# ZED_BREAKOUT_v22.net
KiCad netlist of a schematic drawn in EAGLE
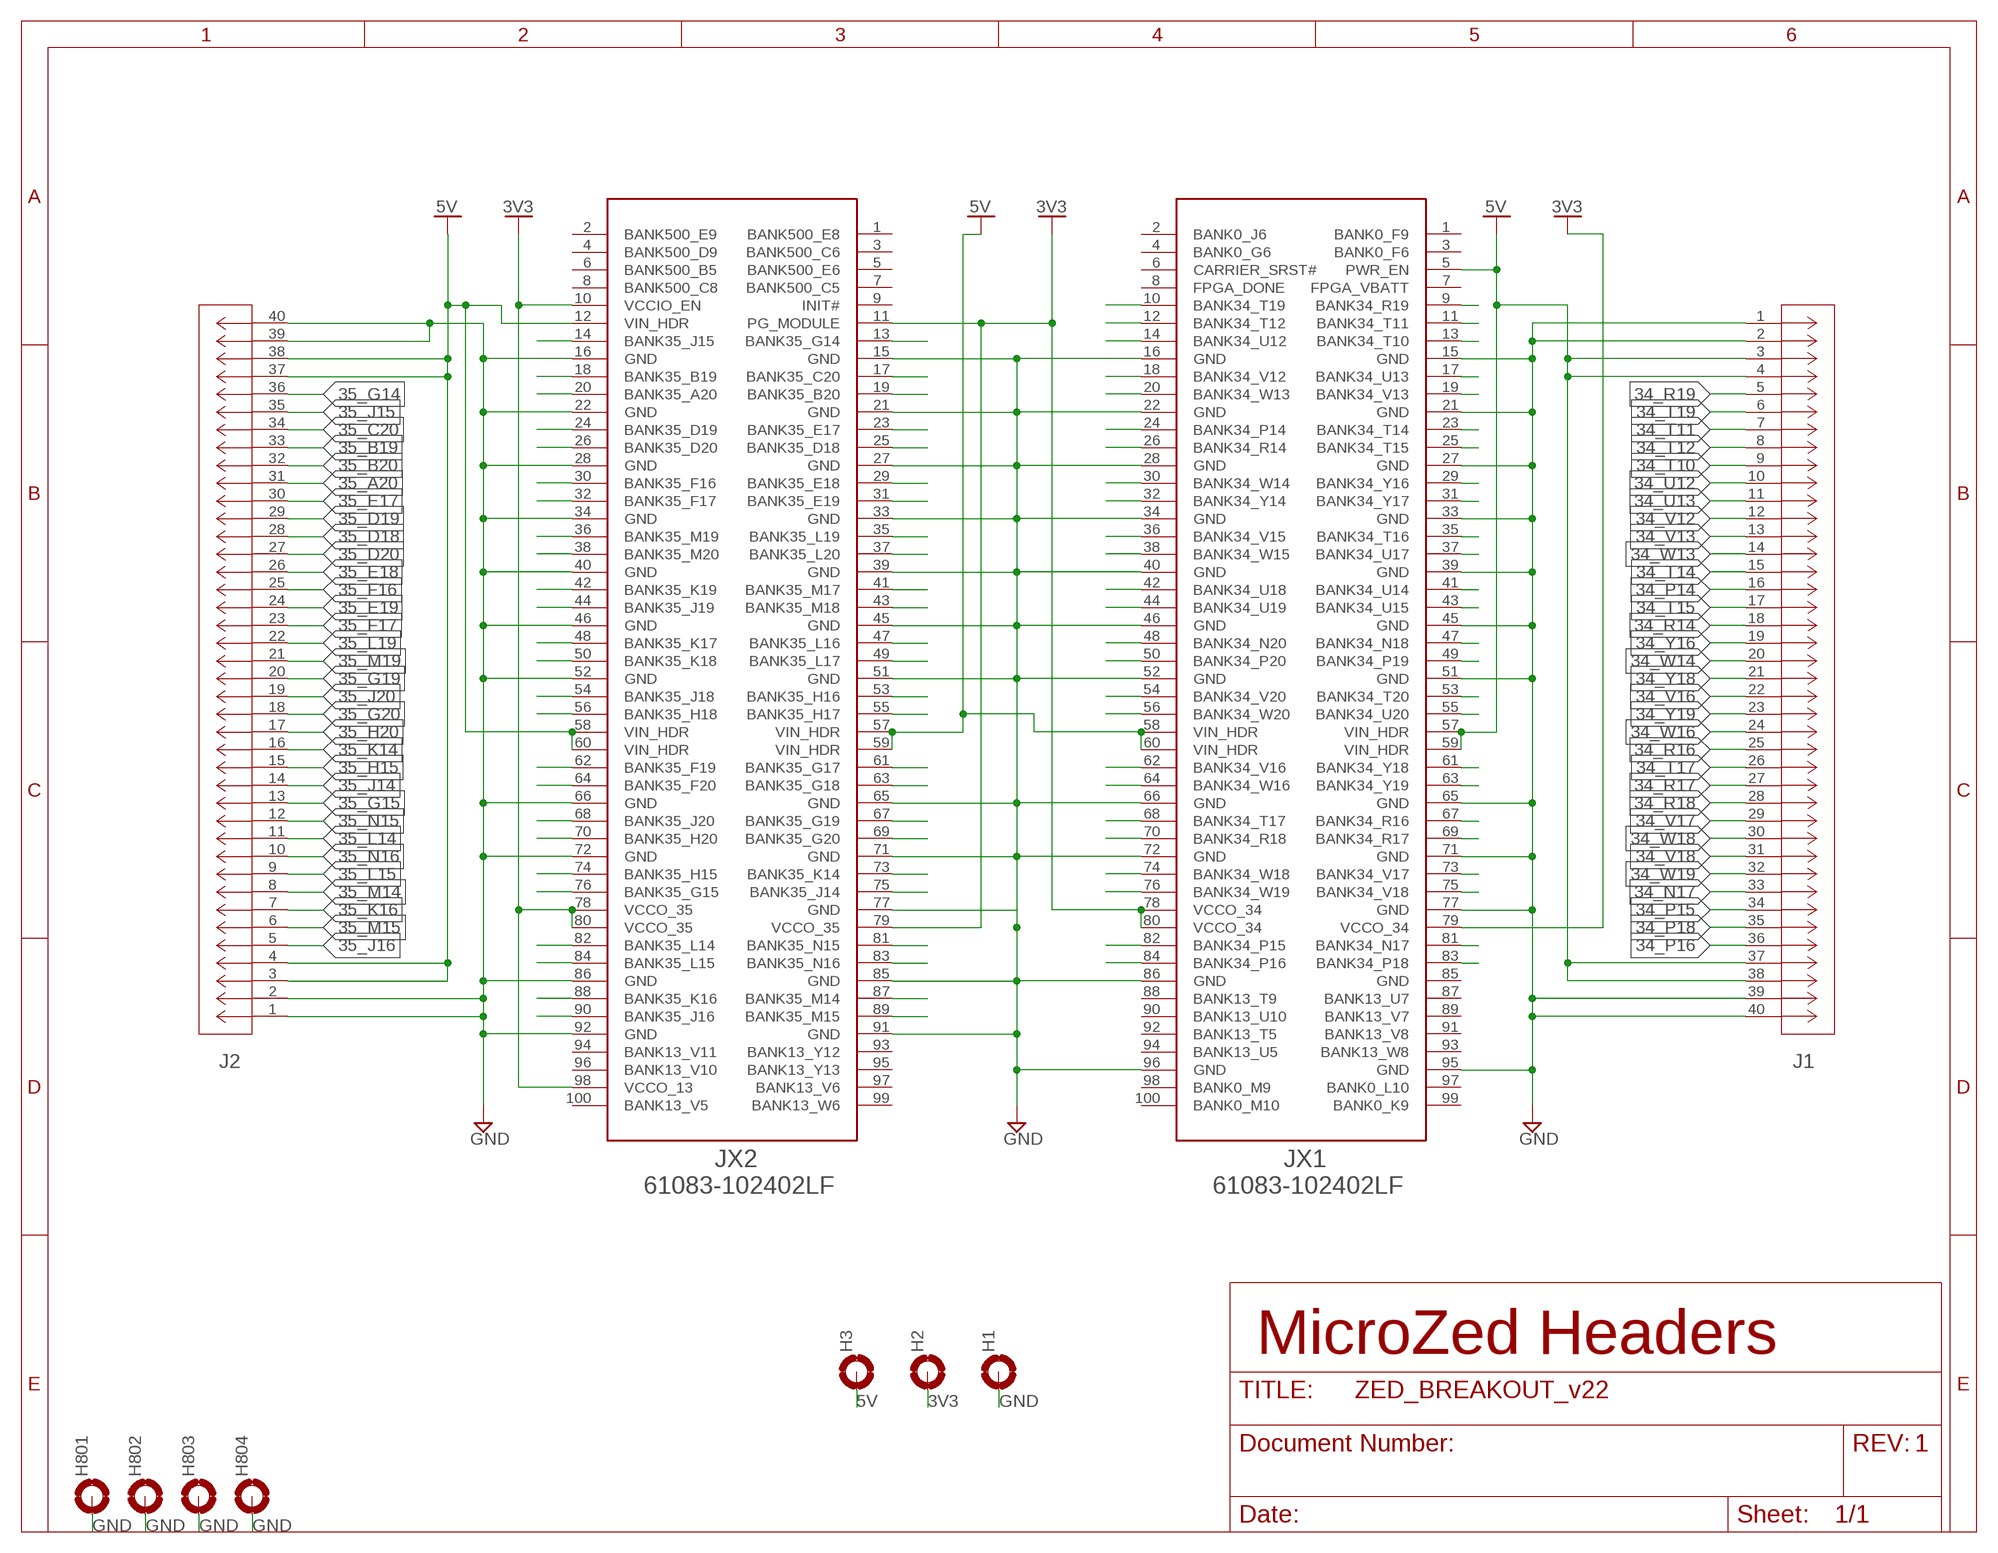
[diagram p0: schematic, sheet 1]

(export (version "E")
  (design (tool "Eeschema 10.0.6"))
  (components
    (comp (ref "H1")
      (value "MOUNT-PAD-ROUND5.0")
      (footprint "eagle-import:5,0-PAD")
      (libsource (lib "eagle-import") (part "MOUNT-PAD-ROUND5.0"))
    )
    (comp (ref "H2")
      (value "MOUNT-PAD-ROUND5.0")
      (footprint "eagle-import:5,0-PAD")
      (libsource (lib "eagle-import") (part "MOUNT-PAD-ROUND5.0"))
    )
    (comp (ref "H3")
      (value "MOUNT-PAD-ROUND5.0")
      (footprint "eagle-import:5,0-PAD")
      (libsource (lib "eagle-import") (part "MOUNT-PAD-ROUND5.0"))
    )
    (comp (ref "H801")
      (value "MOUNT-PAD-ROUND5.0")
      (footprint "eagle-import:5,0-PAD")
      (libsource (lib "eagle-import") (part "MOUNT-PAD-ROUND5.0"))
    )
    (comp (ref "H802")
      (value "MOUNT-PAD-ROUND5.0")
      (footprint "eagle-import:5,0-PAD")
      (libsource (lib "eagle-import") (part "MOUNT-PAD-ROUND5.0"))
    )
    (comp (ref "H803")
      (value "MOUNT-PAD-ROUND5.0")
      (footprint "eagle-import:5,0-PAD")
      (libsource (lib "eagle-import") (part "MOUNT-PAD-ROUND5.0"))
    )
    (comp (ref "H804")
      (value "MOUNT-PAD-ROUND5.0")
      (footprint "eagle-import:5,0-PAD")
      (libsource (lib "eagle-import") (part "MOUNT-PAD-ROUND5.0"))
    )
    (comp (ref "J1")
      (value "TD-120-G-AACON40_2X20_TU_HTS_SAI")
      (footprint "eagle-import:CON40_2X20_TU_HTS_SAI")
      (fields
        (field (name "MANUFACTURER_PART_NUMBER") "TD-120-G-AA")
        (field (name "COPYRIGHT") "Copyright (C) 2024 Ultra Librarian. All rights reserved.")
      )
      (libsource (lib "eagle-import") (part "TD-120-G-AACON40_2X20_TU_HTS_SAI"))
    )
    (comp (ref "J2")
      (value "TD-120-G-AACON40_2X20_TU_HTS_SAI")
      (footprint "eagle-import:CON40_2X20_TU_HTS_SAI")
      (fields
        (field (name "MANUFACTURER_PART_NUMBER") "TD-120-G-AA")
        (field (name "COPYRIGHT") "Copyright (C) 2024 Ultra Librarian. All rights reserved.")
      )
      (libsource (lib "eagle-import") (part "TD-120-G-AACON40_2X20_TU_HTS_SAI"))
    )
    (comp (ref "JX1")
      (value "61083-102402LF")
      (footprint "eagle-import:61083-102402LF")
      (libsource (lib "eagle-import") (part "61083-102402LF-JX1"))
    )
    (comp (ref "JX2")
      (value "61083-102402LF")
      (footprint "eagle-import:61083-102402LF")
      (libsource (lib "eagle-import") (part "61083-102402LF-JX2"))
    )
  )
  (nets
    (net (code "1") (name "3V3") (class "Default")
      (node (ref "H2") (pin "B5") (pinfunction "MOUNT_B5") (pintype "passive"))
      (node (ref "JX1") (pin "78") (pinfunction "VCCO_34_78") (pintype "bidirectional"))
      (node (ref "JX1") (pin "79") (pinfunction "VCCO_34_79") (pintype "bidirectional"))
      (node (ref "JX1") (pin "80") (pinfunction "VCCO_34_80") (pintype "bidirectional"))
      (node (ref "JX2") (pin "10") (pinfunction "VCCIO_EN_10") (pintype "bidirectional"))
      (node (ref "JX2") (pin "11") (pinfunction "PG_MODULE_11") (pintype "bidirectional"))
      (node (ref "JX2") (pin "78") (pinfunction "VCCO_35_78") (pintype "bidirectional"))
      (node (ref "JX2") (pin "79") (pinfunction "VCCO_35_79") (pintype "bidirectional"))
      (node (ref "JX2") (pin "80") (pinfunction "VCCO_35_80") (pintype "bidirectional"))
      (node (ref "JX2") (pin "98") (pinfunction "VCCO_13_98") (pintype "bidirectional"))
    )
    (net (code "2") (name "5V") (class "Default")
      (node (ref "H3") (pin "B5") (pinfunction "MOUNT_B5") (pintype "passive"))
      (node (ref "J1") (pin "3") (pinfunction "3_3") (pintype "passive"))
      (node (ref "J1") (pin "37") (pinfunction "37_37") (pintype "passive"))
      (node (ref "J1") (pin "38") (pinfunction "38_38") (pintype "passive"))
      (node (ref "J1") (pin "4") (pinfunction "4_4") (pintype "passive"))
      (node (ref "J2") (pin "3") (pinfunction "3_3") (pintype "passive"))
      (node (ref "J2") (pin "37") (pinfunction "37_37") (pintype "passive"))
      (node (ref "J2") (pin "38") (pinfunction "38_38") (pintype "passive"))
      (node (ref "J2") (pin "4") (pinfunction "4_4") (pintype "passive"))
      (node (ref "JX1") (pin "5") (pinfunction "PWR_EN_5") (pintype "bidirectional"))
      (node (ref "JX1") (pin "57") (pinfunction "VIN_HDR_57") (pintype "bidirectional"))
      (node (ref "JX1") (pin "58") (pinfunction "VIN_HDR_58") (pintype "bidirectional"))
      (node (ref "JX1") (pin "59") (pinfunction "VIN_HDR_59") (pintype "bidirectional"))
      (node (ref "JX1") (pin "60") (pinfunction "VIN_HDR_60") (pintype "bidirectional"))
      (node (ref "JX2") (pin "12") (pinfunction "VIN_HDR_12") (pintype "bidirectional"))
      (node (ref "JX2") (pin "57") (pinfunction "VIN_HDR_57") (pintype "bidirectional"))
      (node (ref "JX2") (pin "58") (pinfunction "VIN_HDR_58") (pintype "bidirectional"))
      (node (ref "JX2") (pin "59") (pinfunction "VIN_HDR_59") (pintype "bidirectional"))
      (node (ref "JX2") (pin "60") (pinfunction "VIN_HDR_60") (pintype "bidirectional"))
    )
    (net (code "3") (name "34_N17") (class "Default")
      (node (ref "J1") (pin "33") (pinfunction "33_33") (pintype "passive"))
      (node (ref "JX1") (pin "81") (pinfunction "BANK34_N17_81") (pintype "bidirectional"))
    )
    (net (code "4") (name "34_P14") (class "Default")
      (node (ref "J1") (pin "16") (pinfunction "16_16") (pintype "passive"))
      (node (ref "JX1") (pin "24") (pinfunction "BANK34_P14_24") (pintype "bidirectional"))
    )
    (net (code "5") (name "34_P15") (class "Default")
      (node (ref "J1") (pin "34") (pinfunction "34_34") (pintype "passive"))
      (node (ref "JX1") (pin "82") (pinfunction "BANK34_P15_82") (pintype "bidirectional"))
    )
    (net (code "6") (name "34_P16") (class "Default")
      (node (ref "J1") (pin "36") (pinfunction "36_36") (pintype "passive"))
      (node (ref "JX1") (pin "84") (pinfunction "BANK34_P16_84") (pintype "bidirectional"))
    )
    (net (code "7") (name "34_P18") (class "Default")
      (node (ref "J1") (pin "35") (pinfunction "35_35") (pintype "passive"))
      (node (ref "JX1") (pin "83") (pinfunction "BANK34_P18_83") (pintype "bidirectional"))
    )
    (net (code "8") (name "34_R14") (class "Default")
      (node (ref "J1") (pin "18") (pinfunction "18_18") (pintype "passive"))
      (node (ref "JX1") (pin "26") (pinfunction "BANK34_R14_26") (pintype "bidirectional"))
    )
    (net (code "9") (name "34_R16") (class "Default")
      (node (ref "J1") (pin "25") (pinfunction "25_25") (pintype "passive"))
      (node (ref "JX1") (pin "67") (pinfunction "BANK34_R16_67") (pintype "bidirectional"))
    )
    (net (code "10") (name "34_R17") (class "Default")
      (node (ref "J1") (pin "27") (pinfunction "27_27") (pintype "passive"))
      (node (ref "JX1") (pin "69") (pinfunction "BANK34_R17_69") (pintype "bidirectional"))
    )
    (net (code "11") (name "34_R18") (class "Default")
      (node (ref "J1") (pin "28") (pinfunction "28_28") (pintype "passive"))
      (node (ref "JX1") (pin "70") (pinfunction "BANK34_R18_70") (pintype "bidirectional"))
    )
    (net (code "12") (name "34_R19") (class "Default")
      (node (ref "J1") (pin "5") (pinfunction "5_5") (pintype "passive"))
      (node (ref "JX1") (pin "9") (pinfunction "BANK34_R19_9") (pintype "bidirectional"))
    )
    (net (code "13") (name "34_T10") (class "Default")
      (node (ref "J1") (pin "9") (pinfunction "9_9") (pintype "passive"))
      (node (ref "JX1") (pin "13") (pinfunction "BANK34_T10_13") (pintype "bidirectional"))
    )
    (net (code "14") (name "34_T11") (class "Default")
      (node (ref "J1") (pin "7") (pinfunction "7_7") (pintype "passive"))
      (node (ref "JX1") (pin "11") (pinfunction "BANK34_T11_11") (pintype "bidirectional"))
    )
    (net (code "15") (name "34_T12") (class "Default")
      (node (ref "J1") (pin "8") (pinfunction "8_8") (pintype "passive"))
      (node (ref "JX1") (pin "12") (pinfunction "BANK34_T12_12") (pintype "bidirectional"))
    )
    (net (code "16") (name "34_T14") (class "Default")
      (node (ref "J1") (pin "15") (pinfunction "15_15") (pintype "passive"))
      (node (ref "JX1") (pin "23") (pinfunction "BANK34_T14_23") (pintype "bidirectional"))
    )
    (net (code "17") (name "34_T15") (class "Default")
      (node (ref "J1") (pin "17") (pinfunction "17_17") (pintype "passive"))
      (node (ref "JX1") (pin "25") (pinfunction "BANK34_T15_25") (pintype "bidirectional"))
    )
    (net (code "18") (name "34_T17") (class "Default")
      (node (ref "J1") (pin "26") (pinfunction "26_26") (pintype "passive"))
      (node (ref "JX1") (pin "68") (pinfunction "BANK34_T17_68") (pintype "bidirectional"))
    )
    (net (code "19") (name "34_T19") (class "Default")
      (node (ref "J1") (pin "6") (pinfunction "6_6") (pintype "passive"))
      (node (ref "JX1") (pin "10") (pinfunction "BANK34_T19_10") (pintype "bidirectional"))
    )
    (net (code "20") (name "34_U12") (class "Default")
      (node (ref "J1") (pin "10") (pinfunction "10_10") (pintype "passive"))
      (node (ref "JX1") (pin "14") (pinfunction "BANK34_U12_14") (pintype "bidirectional"))
    )
    (net (code "21") (name "34_U13") (class "Default")
      (node (ref "J1") (pin "11") (pinfunction "11_11") (pintype "passive"))
      (node (ref "JX1") (pin "17") (pinfunction "BANK34_U13_17") (pintype "bidirectional"))
    )
    (net (code "22") (name "34_V12") (class "Default")
      (node (ref "J1") (pin "12") (pinfunction "12_12") (pintype "passive"))
      (node (ref "JX1") (pin "18") (pinfunction "BANK34_V12_18") (pintype "bidirectional"))
    )
    (net (code "23") (name "34_V13") (class "Default")
      (node (ref "J1") (pin "13") (pinfunction "13_13") (pintype "passive"))
      (node (ref "JX1") (pin "19") (pinfunction "BANK34_V13_19") (pintype "bidirectional"))
    )
    (net (code "24") (name "34_V16") (class "Default")
      (node (ref "J1") (pin "22") (pinfunction "22_22") (pintype "passive"))
      (node (ref "JX1") (pin "62") (pinfunction "BANK34_V16_62") (pintype "bidirectional"))
    )
    (net (code "25") (name "34_V17") (class "Default")
      (node (ref "J1") (pin "29") (pinfunction "29_29") (pintype "passive"))
      (node (ref "JX1") (pin "73") (pinfunction "BANK34_V17_73") (pintype "bidirectional"))
    )
    (net (code "26") (name "34_V18") (class "Default")
      (node (ref "J1") (pin "31") (pinfunction "31_31") (pintype "passive"))
      (node (ref "JX1") (pin "75") (pinfunction "BANK34_V18_75") (pintype "bidirectional"))
    )
    (net (code "27") (name "34_W13") (class "Default")
      (node (ref "J1") (pin "14") (pinfunction "14_14") (pintype "passive"))
      (node (ref "JX1") (pin "20") (pinfunction "BANK34_W13_20") (pintype "bidirectional"))
    )
    (net (code "28") (name "34_W14") (class "Default")
      (node (ref "J1") (pin "20") (pinfunction "20_20") (pintype "passive"))
      (node (ref "JX1") (pin "30") (pinfunction "BANK34_W14_30") (pintype "bidirectional"))
    )
    (net (code "29") (name "34_W16") (class "Default")
      (node (ref "J1") (pin "24") (pinfunction "24_24") (pintype "passive"))
      (node (ref "JX1") (pin "64") (pinfunction "BANK34_W16_64") (pintype "bidirectional"))
    )
    (net (code "30") (name "34_W18") (class "Default")
      (node (ref "J1") (pin "30") (pinfunction "30_30") (pintype "passive"))
      (node (ref "JX1") (pin "74") (pinfunction "BANK34_W18_74") (pintype "bidirectional"))
    )
    (net (code "31") (name "34_W19") (class "Default")
      (node (ref "J1") (pin "32") (pinfunction "32_32") (pintype "passive"))
      (node (ref "JX1") (pin "76") (pinfunction "BANK34_W19_76") (pintype "bidirectional"))
    )
    (net (code "32") (name "34_Y16") (class "Default")
      (node (ref "J1") (pin "19") (pinfunction "19_19") (pintype "passive"))
      (node (ref "JX1") (pin "29") (pinfunction "BANK34_Y16_29") (pintype "bidirectional"))
    )
    (net (code "33") (name "34_Y18") (class "Default")
      (node (ref "J1") (pin "21") (pinfunction "21_21") (pintype "passive"))
      (node (ref "JX1") (pin "61") (pinfunction "BANK34_Y18_61") (pintype "bidirectional"))
    )
    (net (code "34") (name "34_Y19") (class "Default")
      (node (ref "J1") (pin "23") (pinfunction "23_23") (pintype "passive"))
      (node (ref "JX1") (pin "63") (pinfunction "BANK34_Y19_63") (pintype "bidirectional"))
    )
    (net (code "35") (name "35_A20") (class "Default")
      (node (ref "J2") (pin "31") (pinfunction "31_31") (pintype "passive"))
      (node (ref "JX2") (pin "20") (pinfunction "BANK35_A20_20") (pintype "bidirectional"))
    )
    (net (code "36") (name "35_B19") (class "Default")
      (node (ref "J2") (pin "33") (pinfunction "33_33") (pintype "passive"))
      (node (ref "JX2") (pin "18") (pinfunction "BANK35_B19_18") (pintype "bidirectional"))
    )
    (net (code "37") (name "35_B20") (class "Default")
      (node (ref "J2") (pin "32") (pinfunction "32_32") (pintype "passive"))
      (node (ref "JX2") (pin "19") (pinfunction "BANK35_B20_19") (pintype "bidirectional"))
    )
    (net (code "38") (name "35_C20") (class "Default")
      (node (ref "J2") (pin "34") (pinfunction "34_34") (pintype "passive"))
      (node (ref "JX2") (pin "17") (pinfunction "BANK35_C20_17") (pintype "bidirectional"))
    )
    (net (code "39") (name "35_D18") (class "Default")
      (node (ref "J2") (pin "28") (pinfunction "28_28") (pintype "passive"))
      (node (ref "JX2") (pin "25") (pinfunction "BANK35_D18_25") (pintype "bidirectional"))
    )
    (net (code "40") (name "35_D19") (class "Default")
      (node (ref "J2") (pin "29") (pinfunction "29_29") (pintype "passive"))
      (node (ref "JX2") (pin "24") (pinfunction "BANK35_D19_24") (pintype "bidirectional"))
    )
    (net (code "41") (name "35_D20") (class "Default")
      (node (ref "J2") (pin "27") (pinfunction "27_27") (pintype "passive"))
      (node (ref "JX2") (pin "26") (pinfunction "BANK35_D20_26") (pintype "bidirectional"))
    )
    (net (code "42") (name "35_E17") (class "Default")
      (node (ref "J2") (pin "30") (pinfunction "30_30") (pintype "passive"))
      (node (ref "JX2") (pin "23") (pinfunction "BANK35_E17_23") (pintype "bidirectional"))
    )
    (net (code "43") (name "35_E18") (class "Default")
      (node (ref "J2") (pin "26") (pinfunction "26_26") (pintype "passive"))
      (node (ref "JX2") (pin "29") (pinfunction "BANK35_E18_29") (pintype "bidirectional"))
    )
    (net (code "44") (name "35_E19") (class "Default")
      (node (ref "J2") (pin "24") (pinfunction "24_24") (pintype "passive"))
      (node (ref "JX2") (pin "31") (pinfunction "BANK35_E19_31") (pintype "bidirectional"))
    )
    (net (code "45") (name "35_F16") (class "Default")
      (node (ref "J2") (pin "25") (pinfunction "25_25") (pintype "passive"))
      (node (ref "JX2") (pin "30") (pinfunction "BANK35_F16_30") (pintype "bidirectional"))
    )
    (net (code "46") (name "35_F17") (class "Default")
      (node (ref "J2") (pin "23") (pinfunction "23_23") (pintype "passive"))
      (node (ref "JX2") (pin "32") (pinfunction "BANK35_F17_32") (pintype "bidirectional"))
    )
    (net (code "47") (name "35_G14") (class "Default")
      (node (ref "J2") (pin "36") (pinfunction "36_36") (pintype "passive"))
      (node (ref "JX2") (pin "13") (pinfunction "BANK35_G14_13") (pintype "bidirectional"))
    )
    (net (code "48") (name "35_G15") (class "Default")
      (node (ref "J2") (pin "13") (pinfunction "13_13") (pintype "passive"))
      (node (ref "JX2") (pin "76") (pinfunction "BANK35_G15_76") (pintype "bidirectional"))
    )
    (net (code "49") (name "35_G19") (class "Default")
      (node (ref "J2") (pin "20") (pinfunction "20_20") (pintype "passive"))
      (node (ref "JX2") (pin "67") (pinfunction "BANK35_G19_67") (pintype "bidirectional"))
    )
    (net (code "50") (name "35_G20") (class "Default")
      (node (ref "J2") (pin "18") (pinfunction "18_18") (pintype "passive"))
      (node (ref "JX2") (pin "69") (pinfunction "BANK35_G20_69") (pintype "bidirectional"))
    )
    (net (code "51") (name "35_H15") (class "Default")
      (node (ref "J2") (pin "15") (pinfunction "15_15") (pintype "passive"))
      (node (ref "JX2") (pin "74") (pinfunction "BANK35_H15_74") (pintype "bidirectional"))
    )
    (net (code "52") (name "35_H20") (class "Default")
      (node (ref "J2") (pin "17") (pinfunction "17_17") (pintype "passive"))
      (node (ref "JX2") (pin "70") (pinfunction "BANK35_H20_70") (pintype "bidirectional"))
    )
    (net (code "53") (name "35_J14") (class "Default")
      (node (ref "J2") (pin "14") (pinfunction "14_14") (pintype "passive"))
      (node (ref "JX2") (pin "75") (pinfunction "BANK35_J14_75") (pintype "bidirectional"))
    )
    (net (code "54") (name "35_J15") (class "Default")
      (node (ref "J2") (pin "35") (pinfunction "35_35") (pintype "passive"))
      (node (ref "JX2") (pin "14") (pinfunction "BANK35_J15_14") (pintype "bidirectional"))
    )
    (net (code "55") (name "35_J16") (class "Default")
      (node (ref "J2") (pin "5") (pinfunction "5_5") (pintype "passive"))
      (node (ref "JX2") (pin "90") (pinfunction "BANK35_J16_90") (pintype "bidirectional"))
    )
    (net (code "56") (name "35_J20") (class "Default")
      (node (ref "J2") (pin "19") (pinfunction "19_19") (pintype "passive"))
      (node (ref "JX2") (pin "68") (pinfunction "BANK35_J20_68") (pintype "bidirectional"))
    )
    (net (code "57") (name "35_K14") (class "Default")
      (node (ref "J2") (pin "16") (pinfunction "16_16") (pintype "passive"))
      (node (ref "JX2") (pin "73") (pinfunction "BANK35_K14_73") (pintype "bidirectional"))
    )
    (net (code "58") (name "35_K16") (class "Default")
      (node (ref "J2") (pin "7") (pinfunction "7_7") (pintype "passive"))
      (node (ref "JX2") (pin "88") (pinfunction "BANK35_K16_88") (pintype "bidirectional"))
    )
    (net (code "59") (name "35_L14") (class "Default")
      (node (ref "J2") (pin "11") (pinfunction "11_11") (pintype "passive"))
      (node (ref "JX2") (pin "82") (pinfunction "BANK35_L14_82") (pintype "bidirectional"))
    )
    (net (code "60") (name "35_L15") (class "Default")
      (node (ref "J2") (pin "9") (pinfunction "9_9") (pintype "passive"))
      (node (ref "JX2") (pin "84") (pinfunction "BANK35_L15_84") (pintype "bidirectional"))
    )
    (net (code "61") (name "35_L19") (class "Default")
      (node (ref "J2") (pin "22") (pinfunction "22_22") (pintype "passive"))
      (node (ref "JX2") (pin "35") (pinfunction "BANK35_L19_35") (pintype "bidirectional"))
    )
    (net (code "62") (name "35_M14") (class "Default")
      (node (ref "J2") (pin "8") (pinfunction "8_8") (pintype "passive"))
      (node (ref "JX2") (pin "87") (pinfunction "BANK35_M14_87") (pintype "bidirectional"))
    )
    (net (code "63") (name "35_M15") (class "Default")
      (node (ref "J2") (pin "6") (pinfunction "6_6") (pintype "passive"))
      (node (ref "JX2") (pin "89") (pinfunction "BANK35_M15_89") (pintype "bidirectional"))
    )
    (net (code "64") (name "35_M19") (class "Default")
      (node (ref "J2") (pin "21") (pinfunction "21_21") (pintype "passive"))
      (node (ref "JX2") (pin "36") (pinfunction "BANK35_M19_36") (pintype "bidirectional"))
    )
    (net (code "65") (name "35_N15") (class "Default")
      (node (ref "J2") (pin "12") (pinfunction "12_12") (pintype "passive"))
      (node (ref "JX2") (pin "81") (pinfunction "BANK35_N15_81") (pintype "bidirectional"))
    )
    (net (code "66") (name "35_N16") (class "Default")
      (node (ref "J2") (pin "10") (pinfunction "10_10") (pintype "passive"))
      (node (ref "JX2") (pin "83") (pinfunction "BANK35_N16_83") (pintype "bidirectional"))
    )
    (net (code "67") (name "GND") (class "Default")
      (node (ref "H1") (pin "B5") (pinfunction "MOUNT_B5") (pintype "passive"))
      (node (ref "H801") (pin "B5") (pinfunction "MOUNT_B5") (pintype "passive"))
      (node (ref "H802") (pin "B5") (pinfunction "MOUNT_B5") (pintype "passive"))
      (node (ref "H803") (pin "B5") (pinfunction "MOUNT_B5") (pintype "passive"))
      (node (ref "H804") (pin "B5") (pinfunction "MOUNT_B5") (pintype "passive"))
      (node (ref "J1") (pin "1") (pinfunction "1_1") (pintype "passive"))
      (node (ref "J1") (pin "2") (pinfunction "2_2") (pintype "passive"))
      (node (ref "J1") (pin "39") (pinfunction "39_39") (pintype "passive"))
      (node (ref "J1") (pin "40") (pinfunction "40_40") (pintype "passive"))
      (node (ref "J2") (pin "1") (pinfunction "1_1") (pintype "passive"))
      (node (ref "J2") (pin "2") (pinfunction "2_2") (pintype "passive"))
      (node (ref "J2") (pin "39") (pinfunction "39_39") (pintype "passive"))
      (node (ref "J2") (pin "40") (pinfunction "40_40") (pintype "passive"))
      (node (ref "JX1") (pin "15") (pinfunction "GND_15") (pintype "bidirectional"))
      (node (ref "JX1") (pin "16") (pinfunction "GND_16") (pintype "bidirectional"))
      (node (ref "JX1") (pin "21") (pinfunction "GND_21") (pintype "bidirectional"))
      (node (ref "JX1") (pin "22") (pinfunction "GND_22") (pintype "bidirectional"))
      (node (ref "JX1") (pin "27") (pinfunction "GND_27") (pintype "bidirectional"))
      (node (ref "JX1") (pin "28") (pinfunction "GND_28") (pintype "bidirectional"))
      (node (ref "JX1") (pin "33") (pinfunction "GND_33") (pintype "bidirectional"))
      (node (ref "JX1") (pin "34") (pinfunction "GND_34") (pintype "bidirectional"))
      (node (ref "JX1") (pin "39") (pinfunction "GND_39") (pintype "bidirectional"))
      (node (ref "JX1") (pin "40") (pinfunction "GND_40") (pintype "bidirectional"))
      (node (ref "JX1") (pin "45") (pinfunction "GND_45") (pintype "bidirectional"))
      (node (ref "JX1") (pin "46") (pinfunction "GND_46") (pintype "bidirectional"))
      (node (ref "JX1") (pin "51") (pinfunction "GND_51") (pintype "bidirectional"))
      (node (ref "JX1") (pin "52") (pinfunction "GND_52") (pintype "bidirectional"))
      (node (ref "JX1") (pin "65") (pinfunction "GND_65") (pintype "bidirectional"))
      (node (ref "JX1") (pin "66") (pinfunction "GND_66") (pintype "bidirectional"))
      (node (ref "JX1") (pin "71") (pinfunction "GND_71") (pintype "bidirectional"))
      (node (ref "JX1") (pin "72") (pinfunction "GND_72") (pintype "bidirectional"))
      (node (ref "JX1") (pin "77") (pinfunction "GND_77") (pintype "bidirectional"))
      (node (ref "JX1") (pin "86") (pinfunction "GND_86") (pintype "bidirectional"))
      (node (ref "JX1") (pin "95") (pinfunction "GND_95") (pintype "bidirectional"))
      (node (ref "JX1") (pin "96") (pinfunction "GND_96") (pintype "bidirectional"))
      (node (ref "JX2") (pin "15") (pinfunction "GND_15") (pintype "bidirectional"))
      (node (ref "JX2") (pin "16") (pinfunction "GND_16") (pintype "bidirectional"))
      (node (ref "JX2") (pin "21") (pinfunction "GND_21") (pintype "bidirectional"))
      (node (ref "JX2") (pin "22") (pinfunction "GND_22") (pintype "bidirectional"))
      (node (ref "JX2") (pin "27") (pinfunction "GND_27") (pintype "bidirectional"))
      (node (ref "JX2") (pin "28") (pinfunction "GND_28") (pintype "bidirectional"))
      (node (ref "JX2") (pin "33") (pinfunction "GND_33") (pintype "bidirectional"))
      (node (ref "JX2") (pin "34") (pinfunction "GND_34") (pintype "bidirectional"))
      (node (ref "JX2") (pin "39") (pinfunction "GND_39") (pintype "bidirectional"))
      (node (ref "JX2") (pin "40") (pinfunction "GND_40") (pintype "bidirectional"))
      (node (ref "JX2") (pin "45") (pinfunction "GND_45") (pintype "bidirectional"))
      (node (ref "JX2") (pin "46") (pinfunction "GND_46") (pintype "bidirectional"))
      (node (ref "JX2") (pin "51") (pinfunction "GND_51") (pintype "bidirectional"))
      (node (ref "JX2") (pin "52") (pinfunction "GND_52") (pintype "bidirectional"))
      (node (ref "JX2") (pin "65") (pinfunction "GND_65") (pintype "bidirectional"))
      (node (ref "JX2") (pin "66") (pinfunction "GND_66") (pintype "bidirectional"))
      (node (ref "JX2") (pin "71") (pinfunction "GND_71") (pintype "bidirectional"))
      (node (ref "JX2") (pin "72") (pinfunction "GND_72") (pintype "bidirectional"))
      (node (ref "JX2") (pin "77") (pinfunction "GND_77") (pintype "bidirectional"))
      (node (ref "JX2") (pin "85") (pinfunction "GND_85") (pintype "bidirectional"))
      (node (ref "JX2") (pin "86") (pinfunction "GND_86") (pintype "bidirectional"))
      (node (ref "JX2") (pin "91") (pinfunction "GND_91") (pintype "bidirectional"))
      (node (ref "JX2") (pin "92") (pinfunction "GND_92") (pintype "bidirectional"))
    )
    (net (code "68") (name "unconnected-(JX1-BANK0_F6-Pad3)") (class "Default")
      (node (ref "JX1") (pin "3") (pinfunction "BANK0_F6_3") (pintype "bidirectional"))
    )
    (net (code "69") (name "unconnected-(JX1-BANK0_F9-Pad1)") (class "Default")
      (node (ref "JX1") (pin "1") (pinfunction "BANK0_F9_1") (pintype "bidirectional"))
    )
    (net (code "70") (name "unconnected-(JX1-BANK0_G6-Pad4)") (class "Default")
      (node (ref "JX1") (pin "4") (pinfunction "BANK0_G6_4") (pintype "bidirectional"))
    )
    (net (code "71") (name "unconnected-(JX1-BANK0_J6-Pad2)") (class "Default")
      (node (ref "JX1") (pin "2") (pinfunction "BANK0_J6_2") (pintype "bidirectional"))
    )
    (net (code "72") (name "unconnected-(JX1-BANK0_K9-Pad99)") (class "Default")
      (node (ref "JX1") (pin "99") (pinfunction "BANK0_K9_99") (pintype "bidirectional"))
    )
    (net (code "73") (name "unconnected-(JX1-BANK0_L10-Pad97)") (class "Default")
      (node (ref "JX1") (pin "97") (pinfunction "BANK0_L10_97") (pintype "bidirectional"))
    )
    (net (code "74") (name "unconnected-(JX1-BANK0_M9-Pad98)") (class "Default")
      (node (ref "JX1") (pin "98") (pinfunction "BANK0_M9_98") (pintype "bidirectional"))
    )
    (net (code "75") (name "unconnected-(JX1-BANK0_M10-Pad100)") (class "Default")
      (node (ref "JX1") (pin "100") (pinfunction "BANK0_M10_100") (pintype "bidirectional"))
    )
    (net (code "76") (name "unconnected-(JX1-BANK13_T5-Pad92)") (class "Default")
      (node (ref "JX1") (pin "92") (pinfunction "BANK13_T5_92") (pintype "bidirectional"))
    )
    (net (code "77") (name "unconnected-(JX1-BANK13_T9-Pad88)") (class "Default")
      (node (ref "JX1") (pin "88") (pinfunction "BANK13_T9_88") (pintype "bidirectional"))
    )
    (net (code "78") (name "unconnected-(JX1-BANK13_U5-Pad94)") (class "Default")
      (node (ref "JX1") (pin "94") (pinfunction "BANK13_U5_94") (pintype "bidirectional"))
    )
    (net (code "79") (name "unconnected-(JX1-BANK13_U7-Pad87)") (class "Default")
      (node (ref "JX1") (pin "87") (pinfunction "BANK13_U7_87") (pintype "bidirectional"))
    )
    (net (code "80") (name "unconnected-(JX1-BANK13_U10-Pad90)") (class "Default")
      (node (ref "JX1") (pin "90") (pinfunction "BANK13_U10_90") (pintype "bidirectional"))
    )
    (net (code "81") (name "unconnected-(JX1-BANK13_V7-Pad89)") (class "Default")
      (node (ref "JX1") (pin "89") (pinfunction "BANK13_V7_89") (pintype "bidirectional"))
    )
    (net (code "82") (name "unconnected-(JX1-BANK13_V8-Pad91)") (class "Default")
      (node (ref "JX1") (pin "91") (pinfunction "BANK13_V8_91") (pintype "bidirectional"))
    )
    (net (code "83") (name "unconnected-(JX1-BANK13_W8-Pad93)") (class "Default")
      (node (ref "JX1") (pin "93") (pinfunction "BANK13_W8_93") (pintype "bidirectional"))
    )
    (net (code "84") (name "unconnected-(JX1-BANK34_N18-Pad47)") (class "Default")
      (node (ref "JX1") (pin "47") (pinfunction "BANK34_N18_47") (pintype "bidirectional"))
    )
    (net (code "85") (name "unconnected-(JX1-BANK34_N20-Pad48)") (class "Default")
      (node (ref "JX1") (pin "48") (pinfunction "BANK34_N20_48") (pintype "bidirectional"))
    )
    (net (code "86") (name "unconnected-(JX1-BANK34_P19-Pad49)") (class "Default")
      (node (ref "JX1") (pin "49") (pinfunction "BANK34_P19_49") (pintype "bidirectional"))
    )
    (net (code "87") (name "unconnected-(JX1-BANK34_P20-Pad50)") (class "Default")
      (node (ref "JX1") (pin "50") (pinfunction "BANK34_P20_50") (pintype "bidirectional"))
    )
    (net (code "88") (name "unconnected-(JX1-BANK34_T16-Pad35)") (class "Default")
      (node (ref "JX1") (pin "35") (pinfunction "BANK34_T16_35") (pintype "bidirectional"))
    )
    (net (code "89") (name "unconnected-(JX1-BANK34_T20-Pad53)") (class "Default")
      (node (ref "JX1") (pin "53") (pinfunction "BANK34_T20_53") (pintype "bidirectional"))
    )
    (net (code "90") (name "unconnected-(JX1-BANK34_U14-Pad41)") (class "Default")
      (node (ref "JX1") (pin "41") (pinfunction "BANK34_U14_41") (pintype "bidirectional"))
    )
    (net (code "91") (name "unconnected-(JX1-BANK34_U15-Pad43)") (class "Default")
      (node (ref "JX1") (pin "43") (pinfunction "BANK34_U15_43") (pintype "bidirectional"))
    )
    (net (code "92") (name "unconnected-(JX1-BANK34_U17-Pad37)") (class "Default")
      (node (ref "JX1") (pin "37") (pinfunction "BANK34_U17_37") (pintype "bidirectional"))
    )
    (net (code "93") (name "unconnected-(JX1-BANK34_U18-Pad42)") (class "Default")
      (node (ref "JX1") (pin "42") (pinfunction "BANK34_U18_42") (pintype "bidirectional"))
    )
    (net (code "94") (name "unconnected-(JX1-BANK34_U19-Pad44)") (class "Default")
      (node (ref "JX1") (pin "44") (pinfunction "BANK34_U19_44") (pintype "bidirectional"))
    )
    (net (code "95") (name "unconnected-(JX1-BANK34_U20-Pad55)") (class "Default")
      (node (ref "JX1") (pin "55") (pinfunction "BANK34_U20_55") (pintype "bidirectional"))
    )
    (net (code "96") (name "unconnected-(JX1-BANK34_V15-Pad36)") (class "Default")
      (node (ref "JX1") (pin "36") (pinfunction "BANK34_V15_36") (pintype "bidirectional"))
    )
    (net (code "97") (name "unconnected-(JX1-BANK34_V20-Pad54)") (class "Default")
      (node (ref "JX1") (pin "54") (pinfunction "BANK34_V20_54") (pintype "bidirectional"))
    )
    (net (code "98") (name "unconnected-(JX1-BANK34_W15-Pad38)") (class "Default")
      (node (ref "JX1") (pin "38") (pinfunction "BANK34_W15_38") (pintype "bidirectional"))
    )
    (net (code "99") (name "unconnected-(JX1-BANK34_W20-Pad56)") (class "Default")
      (node (ref "JX1") (pin "56") (pinfunction "BANK34_W20_56") (pintype "bidirectional"))
    )
    (net (code "100") (name "unconnected-(JX1-BANK34_Y14-Pad32)") (class "Default")
      (node (ref "JX1") (pin "32") (pinfunction "BANK34_Y14_32") (pintype "bidirectional"))
    )
    (net (code "101") (name "unconnected-(JX1-BANK34_Y17-Pad31)") (class "Default")
      (node (ref "JX1") (pin "31") (pinfunction "BANK34_Y17_31") (pintype "bidirectional"))
    )
    (net (code "102") (name "unconnected-(JX1-CARRIER_SRST#-Pad6)") (class "Default")
      (node (ref "JX1") (pin "6") (pinfunction "CARRIER_SRST#_6") (pintype "bidirectional"))
    )
    (net (code "103") (name "unconnected-(JX1-FPGA_DONE-Pad8)") (class "Default")
      (node (ref "JX1") (pin "8") (pinfunction "FPGA_DONE_8") (pintype "bidirectional"))
    )
    (net (code "104") (name "unconnected-(JX1-FPGA_VBATT-Pad7)") (class "Default")
      (node (ref "JX1") (pin "7") (pinfunction "FPGA_VBATT_7") (pintype "bidirectional"))
    )
    (net (code "105") (name "unconnected-(JX1-GND-Pad85)") (class "Default")
      (node (ref "JX1") (pin "85") (pinfunction "GND_85") (pintype "bidirectional"))
    )
    (net (code "106") (name "unconnected-(JX2-BANK13_V5-Pad100)") (class "Default")
      (node (ref "JX2") (pin "100") (pinfunction "BANK13_V5_100") (pintype "bidirectional"))
    )
    (net (code "107") (name "unconnected-(JX2-BANK13_V6-Pad97)") (class "Default")
      (node (ref "JX2") (pin "97") (pinfunction "BANK13_V6_97") (pintype "bidirectional"))
    )
    (net (code "108") (name "unconnected-(JX2-BANK13_V10-Pad96)") (class "Default")
      (node (ref "JX2") (pin "96") (pinfunction "BANK13_V10_96") (pintype "bidirectional"))
    )
    (net (code "109") (name "unconnected-(JX2-BANK13_V11-Pad94)") (class "Default")
      (node (ref "JX2") (pin "94") (pinfunction "BANK13_V11_94") (pintype "bidirectional"))
    )
    (net (code "110") (name "unconnected-(JX2-BANK13_W6-Pad99)") (class "Default")
      (node (ref "JX2") (pin "99") (pinfunction "BANK13_W6_99") (pintype "bidirectional"))
    )
    (net (code "111") (name "unconnected-(JX2-BANK13_Y12-Pad93)") (class "Default")
      (node (ref "JX2") (pin "93") (pinfunction "BANK13_Y12_93") (pintype "bidirectional"))
    )
    (net (code "112") (name "unconnected-(JX2-BANK13_Y13-Pad95)") (class "Default")
      (node (ref "JX2") (pin "95") (pinfunction "BANK13_Y13_95") (pintype "bidirectional"))
    )
    (net (code "113") (name "unconnected-(JX2-BANK35_F19-Pad62)") (class "Default")
      (node (ref "JX2") (pin "62") (pinfunction "BANK35_F19_62") (pintype "bidirectional"))
    )
    (net (code "114") (name "unconnected-(JX2-BANK35_F20-Pad64)") (class "Default")
      (node (ref "JX2") (pin "64") (pinfunction "BANK35_F20_64") (pintype "bidirectional"))
    )
    (net (code "115") (name "unconnected-(JX2-BANK35_G17-Pad61)") (class "Default")
      (node (ref "JX2") (pin "61") (pinfunction "BANK35_G17_61") (pintype "bidirectional"))
    )
    (net (code "116") (name "unconnected-(JX2-BANK35_G18-Pad63)") (class "Default")
      (node (ref "JX2") (pin "63") (pinfunction "BANK35_G18_63") (pintype "bidirectional"))
    )
    (net (code "117") (name "unconnected-(JX2-BANK35_H16-Pad53)") (class "Default")
      (node (ref "JX2") (pin "53") (pinfunction "BANK35_H16_53") (pintype "bidirectional"))
    )
    (net (code "118") (name "unconnected-(JX2-BANK35_H17-Pad55)") (class "Default")
      (node (ref "JX2") (pin "55") (pinfunction "BANK35_H17_55") (pintype "bidirectional"))
    )
    (net (code "119") (name "unconnected-(JX2-BANK35_H18-Pad56)") (class "Default")
      (node (ref "JX2") (pin "56") (pinfunction "BANK35_H18_56") (pintype "bidirectional"))
    )
    (net (code "120") (name "unconnected-(JX2-BANK35_J18-Pad54)") (class "Default")
      (node (ref "JX2") (pin "54") (pinfunction "BANK35_J18_54") (pintype "bidirectional"))
    )
    (net (code "121") (name "unconnected-(JX2-BANK35_J19-Pad44)") (class "Default")
      (node (ref "JX2") (pin "44") (pinfunction "BANK35_J19_44") (pintype "bidirectional"))
    )
    (net (code "122") (name "unconnected-(JX2-BANK35_K17-Pad48)") (class "Default")
      (node (ref "JX2") (pin "48") (pinfunction "BANK35_K17_48") (pintype "bidirectional"))
    )
    (net (code "123") (name "unconnected-(JX2-BANK35_K18-Pad50)") (class "Default")
      (node (ref "JX2") (pin "50") (pinfunction "BANK35_K18_50") (pintype "bidirectional"))
    )
    (net (code "124") (name "unconnected-(JX2-BANK35_K19-Pad42)") (class "Default")
      (node (ref "JX2") (pin "42") (pinfunction "BANK35_K19_42") (pintype "bidirectional"))
    )
    (net (code "125") (name "unconnected-(JX2-BANK35_L16-Pad47)") (class "Default")
      (node (ref "JX2") (pin "47") (pinfunction "BANK35_L16_47") (pintype "bidirectional"))
    )
    (net (code "126") (name "unconnected-(JX2-BANK35_L17-Pad49)") (class "Default")
      (node (ref "JX2") (pin "49") (pinfunction "BANK35_L17_49") (pintype "bidirectional"))
    )
    (net (code "127") (name "unconnected-(JX2-BANK35_L20-Pad37)") (class "Default")
      (node (ref "JX2") (pin "37") (pinfunction "BANK35_L20_37") (pintype "bidirectional"))
    )
    (net (code "128") (name "unconnected-(JX2-BANK35_M17-Pad41)") (class "Default")
      (node (ref "JX2") (pin "41") (pinfunction "BANK35_M17_41") (pintype "bidirectional"))
    )
    (net (code "129") (name "unconnected-(JX2-BANK35_M18-Pad43)") (class "Default")
      (node (ref "JX2") (pin "43") (pinfunction "BANK35_M18_43") (pintype "bidirectional"))
    )
    (net (code "130") (name "unconnected-(JX2-BANK35_M20-Pad38)") (class "Default")
      (node (ref "JX2") (pin "38") (pinfunction "BANK35_M20_38") (pintype "bidirectional"))
    )
    (net (code "131") (name "unconnected-(JX2-BANK500_B5-Pad6)") (class "Default")
      (node (ref "JX2") (pin "6") (pinfunction "BANK500_B5_6") (pintype "bidirectional"))
    )
    (net (code "132") (name "unconnected-(JX2-BANK500_C5-Pad7)") (class "Default")
      (node (ref "JX2") (pin "7") (pinfunction "BANK500_C5_7") (pintype "bidirectional"))
    )
    (net (code "133") (name "unconnected-(JX2-BANK500_C6-Pad3)") (class "Default")
      (node (ref "JX2") (pin "3") (pinfunction "BANK500_C6_3") (pintype "bidirectional"))
    )
    (net (code "134") (name "unconnected-(JX2-BANK500_C8-Pad8)") (class "Default")
      (node (ref "JX2") (pin "8") (pinfunction "BANK500_C8_8") (pintype "bidirectional"))
    )
    (net (code "135") (name "unconnected-(JX2-BANK500_D9-Pad4)") (class "Default")
      (node (ref "JX2") (pin "4") (pinfunction "BANK500_D9_4") (pintype "bidirectional"))
    )
    (net (code "136") (name "unconnected-(JX2-BANK500_E6-Pad5)") (class "Default")
      (node (ref "JX2") (pin "5") (pinfunction "BANK500_E6_5") (pintype "bidirectional"))
    )
    (net (code "137") (name "unconnected-(JX2-BANK500_E8-Pad1)") (class "Default")
      (node (ref "JX2") (pin "1") (pinfunction "BANK500_E8_1") (pintype "bidirectional"))
    )
    (net (code "138") (name "unconnected-(JX2-BANK500_E9-Pad2)") (class "Default")
      (node (ref "JX2") (pin "2") (pinfunction "BANK500_E9_2") (pintype "bidirectional"))
    )
    (net (code "139") (name "unconnected-(JX2-INIT#-Pad9)") (class "Default")
      (node (ref "JX2") (pin "9") (pinfunction "INIT#_9") (pintype "bidirectional"))
    )
  )
)
